# optoCouplerDmb.net
KiCad netlist of a schematic drawn in EAGLE
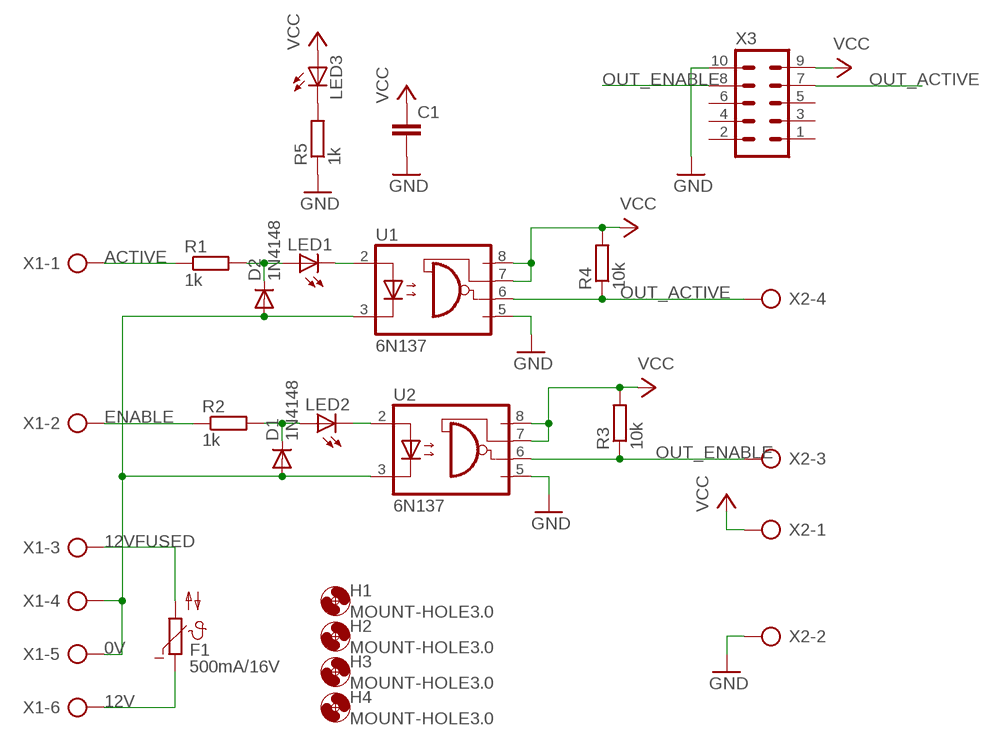
[diagram p0: schematic, sheet 1]

(export (version "E")
  (design (tool "Eeschema 10.0.6"))
  (components
    (comp (ref "C1")
      (value "C-EU050-030X075")
      (footprint "eagle-import:C050-030X075")
      (libsource (lib "eagle-import") (part "C-EU050-030X075"))
    )
    (comp (ref "D1")
      (value "1N4148")
      (footprint "eagle-import:DO35-7")
      (libsource (lib "eagle-import") (part "1N4148DO35-7"))
    )
    (comp (ref "D2")
      (value "1N4148")
      (footprint "eagle-import:DO35-7")
      (libsource (lib "eagle-import") (part "1N4148DO35-7"))
    )
    (comp (ref "F1")
      (value "500mA/16V")
      (footprint "eagle-import:B57164")
      (fields (field (name "MPN") "B57164K474K52"))
      (libsource (lib "eagle-import") (part "B57164"))
    )
    (comp (ref "H1")
      (value "MOUNT-HOLE3.0")
      (footprint "eagle-import:3,0")
      (libsource (lib "eagle-import") (part "MOUNT-HOLE3.0"))
    )
    (comp (ref "H2")
      (value "MOUNT-HOLE3.0")
      (footprint "eagle-import:3,0")
      (libsource (lib "eagle-import") (part "MOUNT-HOLE3.0"))
    )
    (comp (ref "H3")
      (value "MOUNT-HOLE3.0")
      (footprint "eagle-import:3,0")
      (libsource (lib "eagle-import") (part "MOUNT-HOLE3.0"))
    )
    (comp (ref "H4")
      (value "MOUNT-HOLE3.0")
      (footprint "eagle-import:3,0")
      (libsource (lib "eagle-import") (part "MOUNT-HOLE3.0"))
    )
    (comp (ref "LED1")
      (value "LED3MM")
      (footprint "eagle-import:LED3MM")
      (libsource (lib "eagle-import") (part "LED3MM"))
    )
    (comp (ref "LED2")
      (value "LED3MM")
      (footprint "eagle-import:LED3MM")
      (libsource (lib "eagle-import") (part "LED3MM"))
    )
    (comp (ref "LED3")
      (value "LED3MM")
      (footprint "eagle-import:LED3MM")
      (libsource (lib "eagle-import") (part "LED3MM"))
    )
    (comp (ref "R1")
      (value "1k")
      (footprint "eagle-import:0207_10")
      (libsource (lib "eagle-import") (part "R-EU_0207/10"))
    )
    (comp (ref "R2")
      (value "1k")
      (footprint "eagle-import:0207_10")
      (libsource (lib "eagle-import") (part "R-EU_0207/10"))
    )
    (comp (ref "R3")
      (value "10k")
      (footprint "eagle-import:0207_10")
      (libsource (lib "eagle-import") (part "R-EU_0207/10"))
    )
    (comp (ref "R4")
      (value "10k")
      (footprint "eagle-import:0207_10")
      (libsource (lib "eagle-import") (part "R-EU_0207/10"))
    )
    (comp (ref "R5")
      (value "1k")
      (footprint "eagle-import:0207_10")
      (libsource (lib "eagle-import") (part "R-EU_0207/10"))
    )
    (comp (ref "U1")
      (value "6N137")
      (footprint "eagle-import:DIL08")
      (libsource (lib "eagle-import") (part "6N137"))
    )
    (comp (ref "U2")
      (value "6N137")
      (footprint "eagle-import:DIL08")
      (libsource (lib "eagle-import") (part "6N137"))
    )
    (comp (ref "X1")
      (value "AK500/6")
      (footprint "eagle-import:AK500_6")
      (libsource (lib "eagle-import") (part "AK500/6"))
    )
    (comp (ref "X2")
      (value "AK500/4")
      (footprint "eagle-import:AK500_4")
      (libsource (lib "eagle-import") (part "AK500/4"))
    )
    (comp (ref "X3")
      (value "ML10")
      (footprint "eagle-import:ML10")
      (libsource (lib "eagle-import") (part "ML10"))
    )
  )
  (nets
    (net (code "1") (name "/0V") (class "Default")
      (node (ref "D1") (pin "A") (pinfunction "A_A") (pintype "passive"))
      (node (ref "D2") (pin "A") (pinfunction "A_A") (pintype "passive"))
      (node (ref "U1") (pin "3") (pinfunction "C_3") (pintype "passive"))
      (node (ref "U2") (pin "3") (pinfunction "C_3") (pintype "passive"))
      (node (ref "X1") (pin "4") (pinfunction "KL_4") (pintype "passive"))
      (node (ref "X1") (pin "5") (pinfunction "KL_5") (pintype "passive"))
    )
    (net (code "2") (name "/12V") (class "Default")
      (node (ref "F1") (pin "1") (pinfunction "1_1") (pintype "passive"))
      (node (ref "X1") (pin "6") (pinfunction "KL_6") (pintype "passive"))
    )
    (net (code "3") (name "/12VFUSED") (class "Default")
      (node (ref "F1") (pin "2") (pinfunction "2_2") (pintype "passive"))
      (node (ref "X1") (pin "3") (pinfunction "KL_3") (pintype "passive"))
    )
    (net (code "4") (name "/ACTIVE") (class "Default")
      (node (ref "R1") (pin "1") (pinfunction "1_1") (pintype "passive"))
      (node (ref "X1") (pin "1") (pinfunction "KL_1") (pintype "passive"))
    )
    (net (code "5") (name "/ENABLE") (class "Default")
      (node (ref "R2") (pin "1") (pinfunction "1_1") (pintype "passive"))
      (node (ref "X1") (pin "2") (pinfunction "KL_2") (pintype "passive"))
    )
    (net (code "6") (name "/OUT_ACTIVE") (class "Default")
      (node (ref "R4") (pin "1") (pinfunction "1_1") (pintype "passive"))
      (node (ref "U1") (pin "6") (pinfunction "VO_6") (pintype "passive"))
      (node (ref "X2") (pin "4") (pinfunction "KL_4") (pintype "passive"))
      (node (ref "X3") (pin "7") (pinfunction "7_7") (pintype "passive"))
    )
    (net (code "7") (name "/OUT_ENABLE") (class "Default")
      (node (ref "R3") (pin "1") (pinfunction "1_1") (pintype "passive"))
      (node (ref "U2") (pin "6") (pinfunction "VO_6") (pintype "passive"))
      (node (ref "X2") (pin "3") (pinfunction "KL_3") (pintype "passive"))
      (node (ref "X3") (pin "8") (pinfunction "8_8") (pintype "passive"))
    )
    (net (code "8") (name "GND") (class "Default")
      (node (ref "C1") (pin "2") (pinfunction "2_2") (pintype "passive"))
      (node (ref "R5") (pin "1") (pinfunction "1_1") (pintype "passive"))
      (node (ref "U1") (pin "5") (pinfunction "GND_5") (pintype "passive"))
      (node (ref "U2") (pin "5") (pinfunction "GND_5") (pintype "passive"))
      (node (ref "X2") (pin "2") (pinfunction "KL_2") (pintype "passive"))
      (node (ref "X3") (pin "10") (pinfunction "10_10") (pintype "passive"))
    )
    (net (code "9") (name "Net-(D1-PadC)") (class "Default")
      (node (ref "D1") (pin "C") (pinfunction "C_C") (pintype "passive"))
      (node (ref "LED2") (pin "A") (pinfunction "A_A") (pintype "passive"))
      (node (ref "R2") (pin "2") (pinfunction "2_2") (pintype "passive"))
    )
    (net (code "10") (name "Net-(D2-PadC)") (class "Default")
      (node (ref "D2") (pin "C") (pinfunction "C_C") (pintype "passive"))
      (node (ref "LED1") (pin "A") (pinfunction "A_A") (pintype "passive"))
      (node (ref "R1") (pin "2") (pinfunction "2_2") (pintype "passive"))
    )
    (net (code "11") (name "Net-(LED1-C)") (class "Default")
      (node (ref "LED1") (pin "K") (pinfunction "C_K") (pintype "passive"))
      (node (ref "U1") (pin "2") (pinfunction "A_2") (pintype "passive"))
    )
    (net (code "12") (name "Net-(LED2-C)") (class "Default")
      (node (ref "LED2") (pin "K") (pinfunction "C_K") (pintype "passive"))
      (node (ref "U2") (pin "2") (pinfunction "A_2") (pintype "passive"))
    )
    (net (code "13") (name "Net-(LED3-C)") (class "Default")
      (node (ref "LED3") (pin "K") (pinfunction "C_K") (pintype "passive"))
      (node (ref "R5") (pin "2") (pinfunction "2_2") (pintype "passive"))
    )
    (net (code "14") (name "VCC") (class "Default")
      (node (ref "C1") (pin "1") (pinfunction "1_1") (pintype "passive"))
      (node (ref "LED3") (pin "A") (pinfunction "A_A") (pintype "passive"))
      (node (ref "R3") (pin "2") (pinfunction "2_2") (pintype "passive"))
      (node (ref "R4") (pin "2") (pinfunction "2_2") (pintype "passive"))
      (node (ref "U1") (pin "7") (pinfunction "VE_7") (pintype "passive"))
      (node (ref "U1") (pin "8") (pinfunction "VCC_8") (pintype "passive"))
      (node (ref "U2") (pin "7") (pinfunction "VE_7") (pintype "passive"))
      (node (ref "U2") (pin "8") (pinfunction "VCC_8") (pintype "passive"))
      (node (ref "X2") (pin "1") (pinfunction "KL_1") (pintype "passive"))
      (node (ref "X3") (pin "9") (pinfunction "9_9") (pintype "passive"))
    )
    (net (code "15") (name "unconnected-(X3-Pad1)") (class "Default")
      (node (ref "X3") (pin "1") (pinfunction "1_1") (pintype "passive"))
    )
    (net (code "16") (name "unconnected-(X3-Pad2)") (class "Default")
      (node (ref "X3") (pin "2") (pinfunction "2_2") (pintype "passive"))
    )
    (net (code "17") (name "unconnected-(X3-Pad3)") (class "Default")
      (node (ref "X3") (pin "3") (pinfunction "3_3") (pintype "passive"))
    )
    (net (code "18") (name "unconnected-(X3-Pad4)") (class "Default")
      (node (ref "X3") (pin "4") (pinfunction "4_4") (pintype "passive"))
    )
    (net (code "19") (name "unconnected-(X3-Pad5)") (class "Default")
      (node (ref "X3") (pin "5") (pinfunction "5_5") (pintype "passive"))
    )
    (net (code "20") (name "unconnected-(X3-Pad6)") (class "Default")
      (node (ref "X3") (pin "6") (pinfunction "6_6") (pintype "passive"))
    )
  )
)
